# Power_Board_DRV8323.net
KiCad netlist of a schematic drawn in Altium Designer
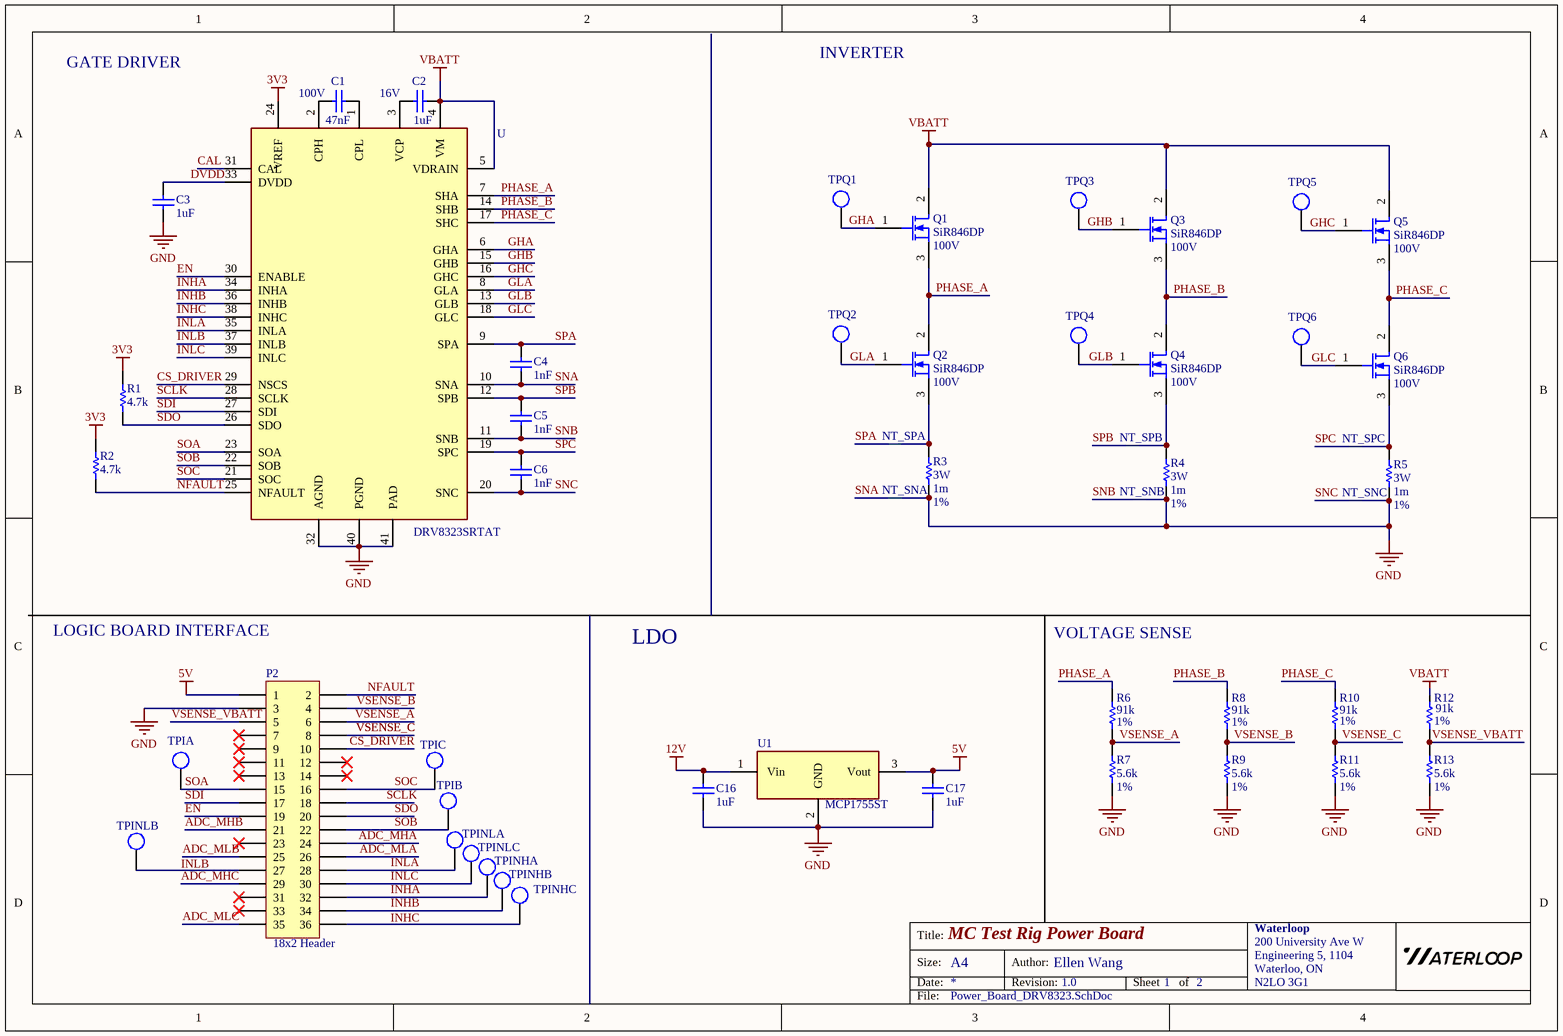
[diagram p0: Power_Board_DRV8323.SchDoc]

(export (version "E")
  (design (tool "Eeschema 10.0.6"))
  (components
    (comp (ref "C1")
      (value "47nF")
      (footprint "0805 - Capacitor")
      (description "Nonpolarized Capacitor")
      (fields
        (field (name "MANUFACTURER") "YAGEO")
        (field (name "RATING") "100V")
        (field (name "MANUFACTURER PART NUMBER") "CC0805KKX7R0BB473")
      )
      (libsource (lib "General") (part "Capacitor - Nonpolarized"))
    )
    (comp (ref "C2")
      (value "1uF")
      (footprint "0805 - Capacitor")
      (description "Nonpolarized Capacitor")
      (fields
        (field (name "MANUFACTURER") "YAGEO")
        (field (name "RATING") "16V")
        (field (name "MANUFACTURER PART NUMBER") "CC0805KKX7R7BB105")
      )
      (libsource (lib "General") (part "Capacitor - Nonpolarized"))
    )
    (comp (ref "C3")
      (value "1uF")
      (footprint "0805 - Capacitor")
      (description "Nonpolarized Capacitor")
      (fields
        (field (name "MANUFACTURER") "YAGEO")
        (field (name "MANUFACTURER PART NUMBER") "CC0805KKX7R7BB105")
      )
      (libsource (lib "General") (part "Capacitor - Nonpolarized"))
    )
    (comp (ref "C4")
      (value "1nF")
      (footprint "0805 - Capacitor")
      (description "Nonpolarized Capacitor")
      (fields
        (field (name "MANUFACTURER") "YAGEO")
        (field (name "MANUFACTURER PART NUMBER") "CC0805KRX7R0BB102")
      )
      (libsource (lib "General") (part "Capacitor - Nonpolarized"))
    )
    (comp (ref "C5")
      (value "1nF")
      (footprint "0805 - Capacitor")
      (description "Nonpolarized Capacitor")
      (fields
        (field (name "MANUFACTURER") "YAGEO")
        (field (name "MANUFACTURER PART NUMBER") "CC0805KRX7R0BB102")
      )
      (libsource (lib "General") (part "Capacitor - Nonpolarized"))
    )
    (comp (ref "C6")
      (value "1nF")
      (footprint "0805 - Capacitor")
      (description "Nonpolarized Capacitor")
      (fields
        (field (name "MANUFACTURER") "YAGEO")
        (field (name "MANUFACTURER PART NUMBER") "CC0805KRX7R0BB102")
      )
      (libsource (lib "General") (part "Capacitor - Nonpolarized"))
    )
    (comp (ref "C16")
      (value "1uF")
      (footprint "0805 - Capacitor")
      (description "Nonpolarized Capacitor")
      (fields (field (name "Comment") "Capacitor - Nonpolarized"))
      (libsource (lib "General") (part "Capacitor - Nonpolarized"))
    )
    (comp (ref "C17")
      (value "1uF")
      (footprint "0805 - Capacitor")
      (description "Nonpolarized Capacitor")
      (fields (field (name "Comment") "Capacitor - Nonpolarized"))
      (libsource (lib "General") (part "Capacitor - Nonpolarized"))
    )
    (comp (ref "NT_SNA") (value "NetTie") (footprint "Net Tie") (libsource (lib "General") (part "Net Tie")))
    (comp (ref "NT_SNB") (value "NetTie") (footprint "Net Tie") (libsource (lib "General") (part "Net Tie")))
    (comp (ref "NT_SNC") (value "NetTie") (footprint "Net Tie") (libsource (lib "General") (part "Net Tie")))
    (comp (ref "NT_SPA") (value "NetTie") (footprint "Net Tie") (libsource (lib "General") (part "Net Tie")))
    (comp (ref "NT_SPB") (value "NetTie") (footprint "Net Tie") (libsource (lib "General") (part "Net Tie")))
    (comp (ref "NT_SPC") (value "NetTie") (footprint "Net Tie") (libsource (lib "General") (part "Net Tie")))
    (comp (ref "P2")
      (value "Header 18X2")
      (footprint "HDR2X18")
      (description "Header, 18-Pin, Dual row")
      (fields (field (name "PUBLISHER") "Altium Limited"))
      (libsource (lib "Miscellaneous Connectors") (part "Header 18X2"))
    )
    (comp (ref "Q1")
      (value "MOSFET-N")
      (footprint "PowerPAK® SO-8")
      (description "N-Channel MOSFET")
      (fields (field (name "SUPPLIER PART NUMBER") "SiR846DP") (field (name "RATING") "100V"))
      (libsource (lib "General") (part "MOSFET-N"))
    )
    (comp (ref "Q2")
      (value "MOSFET-N")
      (footprint "PowerPAK® SO-8")
      (description "N-Channel MOSFET")
      (fields (field (name "SUPPLIER PART NUMBER") "SiR846DP") (field (name "RATING") "100V"))
      (libsource (lib "General") (part "MOSFET-N"))
    )
    (comp (ref "Q3")
      (value "MOSFET-N")
      (footprint "PowerPAK® SO-8")
      (description "N-Channel MOSFET")
      (fields (field (name "SUPPLIER PART NUMBER") "SiR846DP") (field (name "RATING") "100V"))
      (libsource (lib "General") (part "MOSFET-N"))
    )
    (comp (ref "Q4")
      (value "MOSFET-N")
      (footprint "PowerPAK® SO-8")
      (description "N-Channel MOSFET")
      (fields (field (name "SUPPLIER PART NUMBER") "SiR846DP") (field (name "RATING") "100V"))
      (libsource (lib "General") (part "MOSFET-N"))
    )
    (comp (ref "Q5")
      (value "MOSFET-N")
      (footprint "PowerPAK® SO-8")
      (description "N-Channel MOSFET")
      (fields (field (name "SUPPLIER PART NUMBER") "SiR846DP") (field (name "RATING") "100V"))
      (libsource (lib "General") (part "MOSFET-N"))
    )
    (comp (ref "Q6")
      (value "MOSFET-N")
      (footprint "PowerPAK® SO-8")
      (description "N-Channel MOSFET")
      (fields (field (name "SUPPLIER PART NUMBER") "SiR846DP") (field (name "RATING") "100V"))
      (libsource (lib "General") (part "MOSFET-N"))
    )
    (comp (ref "R1")
      (value "4.7k")
      (footprint "0603 - Resistor")
      (description "Resistor")
      (fields
        (field (name "MANUFACTURER PART NUMBER") "RC0603FR-074K7L")
        (field (name "MANUFACTURER") "YAGEO")
      )
      (libsource (lib "General") (part "Resistor"))
    )
    (comp (ref "R2")
      (value "4.7k")
      (footprint "0603 - Resistor")
      (description "Resistor")
      (fields
        (field (name "MANUFACTURER PART NUMBER") "RC0603FR-074K7L")
        (field (name "MANUFACTURER") "YAGEO")
      )
      (libsource (lib "General") (part "Resistor"))
    )
    (comp (ref "R3")
      (value "1m")
      (footprint "2512 - RESISTOR")
      (description "Resistor")
      (fields
        (field (name "RATING") "3W")
        (field (name "MANUFACTURER PART NUMBER") "CSR2512C0R001F")
        (field (name "MANUFACTURER") "Riedon")
        (field (name "TOLERANCE") "1%")
      )
      (libsource (lib "General") (part "Resistor"))
    )
    (comp (ref "R4")
      (value "1m")
      (footprint "2512 - RESISTOR")
      (description "Resistor")
      (fields
        (field (name "RATING") "3W")
        (field (name "MANUFACTURER PART NUMBER") "CSR2512C0R001F")
        (field (name "MANUFACTURER") "Riedon")
        (field (name "TOLERANCE") "1%")
      )
      (libsource (lib "General") (part "Resistor"))
    )
    (comp (ref "R5")
      (value "1m")
      (footprint "2512 - RESISTOR")
      (description "Resistor")
      (fields
        (field (name "RATING") "3W")
        (field (name "MANUFACTURER PART NUMBER") "CSR2512C0R001F")
        (field (name "MANUFACTURER") "Riedon")
        (field (name "TOLERANCE") "1%")
      )
      (libsource (lib "General") (part "Resistor"))
    )
    (comp (ref "R6")
      (value "91k")
      (footprint "0603 - Resistor")
      (description "Resistor")
      (fields
        (field (name "MANUFACTURER PART NUMBER") "RC0603FR-0791KL")
        (field (name "MANUFACTURER") "YAGEO")
        (field (name "TOLERANCE") "1%")
      )
      (libsource (lib "General") (part "Resistor"))
    )
    (comp (ref "R7")
      (value "5.6k")
      (footprint "0603 - Resistor")
      (description "Resistor")
      (fields
        (field (name "MANUFACTURER PART NUMBER") "RC0603FR-075K6L")
        (field (name "MANUFACTURER") "YAGEO")
        (field (name "TOLERANCE") "1%")
      )
      (libsource (lib "General") (part "Resistor"))
    )
    (comp (ref "R8")
      (value "91k")
      (footprint "0603 - Resistor")
      (description "Resistor")
      (fields
        (field (name "MANUFACTURER PART NUMBER") "RC0603FR-0791KL")
        (field (name "MANUFACTURER") "YAGEO")
        (field (name "TOLERANCE") "1%")
      )
      (libsource (lib "General") (part "Resistor"))
    )
    (comp (ref "R9")
      (value "5.6k")
      (footprint "0603 - Resistor")
      (description "Resistor")
      (fields
        (field (name "MANUFACTURER PART NUMBER") "RC0603FR-075K6L")
        (field (name "MANUFACTURER") "YAGEO")
        (field (name "TOLERANCE") "1%")
      )
      (libsource (lib "General") (part "Resistor"))
    )
    (comp (ref "R10")
      (value "91k")
      (footprint "0603 - Resistor")
      (description "Resistor")
      (fields
        (field (name "MANUFACTURER PART NUMBER") "RC0603FR-0791KL")
        (field (name "MANUFACTURER") "YAGEO")
        (field (name "TOLERANCE") "1%")
      )
      (libsource (lib "General") (part "Resistor"))
    )
    (comp (ref "R11")
      (value "5.6k")
      (footprint "0603 - Resistor")
      (description "Resistor")
      (fields
        (field (name "MANUFACTURER PART NUMBER") "RC0603FR-075K6L")
        (field (name "MANUFACTURER") "YAGEO")
        (field (name "TOLERANCE") "1%")
      )
      (libsource (lib "General") (part "Resistor"))
    )
    (comp (ref "R12")
      (value "91k")
      (footprint "0603 - Resistor")
      (description "Resistor")
      (fields
        (field (name "MANUFACTURER PART NUMBER") "RC0603FR-0791KL")
        (field (name "MANUFACTURER") "YAGEO")
        (field (name "TOLERANCE") "1%")
      )
      (libsource (lib "General") (part "Resistor"))
    )
    (comp (ref "R13")
      (value "5.6k")
      (footprint "0603 - Resistor")
      (description "Resistor")
      (fields
        (field (name "MANUFACTURER PART NUMBER") "RC0603FR-075K6L")
        (field (name "MANUFACTURER") "YAGEO")
        (field (name "TOLERANCE") "1%")
      )
      (libsource (lib "General") (part "Resistor"))
    )
    (comp (ref "TPIA")
      (value "Test Point")
      (footprint "Test Point")
      (libsource (lib "General") (part "Test Point"))
    )
    (comp (ref "TPIB")
      (value "Test Point")
      (footprint "Test Point")
      (libsource (lib "General") (part "Test Point"))
    )
    (comp (ref "TPIC")
      (value "Test Point")
      (footprint "Test Point")
      (libsource (lib "General") (part "Test Point"))
    )
    (comp (ref "TPINHA")
      (value "Test Point")
      (footprint "Test Point")
      (libsource (lib "General") (part "Test Point"))
    )
    (comp (ref "TPINHB")
      (value "Test Point")
      (footprint "Test Point")
      (libsource (lib "General") (part "Test Point"))
    )
    (comp (ref "TPINHC")
      (value "Test Point")
      (footprint "Test Point")
      (libsource (lib "General") (part "Test Point"))
    )
    (comp (ref "TPINLA")
      (value "Test Point")
      (footprint "Test Point")
      (libsource (lib "General") (part "Test Point"))
    )
    (comp (ref "TPINLB")
      (value "Test Point")
      (footprint "Test Point")
      (libsource (lib "General") (part "Test Point"))
    )
    (comp (ref "TPINLC")
      (value "Test Point")
      (footprint "Test Point")
      (libsource (lib "General") (part "Test Point"))
    )
    (comp (ref "TPQ1")
      (value "Test Point")
      (footprint "Test Point")
      (libsource (lib "General") (part "Test Point"))
    )
    (comp (ref "TPQ2")
      (value "Test Point")
      (footprint "Test Point")
      (libsource (lib "General") (part "Test Point"))
    )
    (comp (ref "TPQ3")
      (value "Test Point")
      (footprint "Test Point")
      (libsource (lib "General") (part "Test Point"))
    )
    (comp (ref "TPQ4")
      (value "Test Point")
      (footprint "Test Point")
      (libsource (lib "General") (part "Test Point"))
    )
    (comp (ref "TPQ5")
      (value "Test Point")
      (footprint "Test Point")
      (libsource (lib "General") (part "Test Point"))
    )
    (comp (ref "TPQ6")
      (value "Test Point")
      (footprint "Test Point")
      (libsource (lib "General") (part "Test Point"))
    )
    (comp (ref "U")
      (value "DRV8323SRTAT")
      (footprint "DRV8323SRTAT")
      (description "Multiphase Motor Driver Power MOSFET SPI")
      (fields (field (name "MANUFACTURER") "Texas Instruments"))
      (libsource (lib "MC") (part "DRV8323SRTAT"))
    )
    (comp (ref "U1")
      (value "MCP1755ST")
      (footprint "MCP1755ST")
      (libsource (lib "GeneralComponents") (part "MCP1755ST"))
    )
  )
  (nets
    (net (code "1") (name "/ADC_MHA") (class "Default")
      (node (ref "P2") (pin "24") (pinfunction "24_24") (pintype "passive"))
    )
    (net (code "2") (name "/ADC_MHB") (class "Default")
      (node (ref "P2") (pin "21") (pinfunction "21_21") (pintype "passive"))
    )
    (net (code "3") (name "/ADC_MHC") (class "Default")
      (node (ref "P2") (pin "29") (pinfunction "29_29") (pintype "passive"))
    )
    (net (code "4") (name "/ADC_MLA") (class "Default")
      (node (ref "P2") (pin "26") (pinfunction "26_26") (pintype "passive"))
    )
    (net (code "5") (name "/ADC_MLB") (class "Default")
      (node (ref "P2") (pin "25") (pinfunction "25_25") (pintype "passive"))
    )
    (net (code "6") (name "/ADC_MLC") (class "Default")
      (node (ref "P2") (pin "35") (pinfunction "35_35") (pintype "passive"))
    )
    (net (code "7") (name "/CAL") (class "Default")
      (node (ref "U") (pin "31") (pinfunction "CAL_31") (pintype "passive"))
    )
    (net (code "8") (name "/CS_DRIVER") (class "Default")
      (node (ref "P2") (pin "10") (pinfunction "10_10") (pintype "passive"))
      (node (ref "U") (pin "29") (pinfunction "NSCS_29") (pintype "passive"))
    )
    (net (code "9") (name "/DVDD") (class "Default")
      (node (ref "C3") (pin "2") (pinfunction "2_2") (pintype "passive"))
      (node (ref "U") (pin "33") (pinfunction "DVDD_33") (pintype "power_in"))
    )
    (net (code "10") (name "/EN") (class "Default")
      (node (ref "P2") (pin "19") (pinfunction "19_19") (pintype "passive"))
      (node (ref "U") (pin "30") (pinfunction "ENABLE_30") (pintype "passive"))
    )
    (net (code "11") (name "/GHA") (class "Default")
      (node (ref "Q1") (pin "1") (pinfunction "G_1") (pintype "passive"))
      (node (ref "TPQ1") (pin "1") (pinfunction "0_1") (pintype "passive"))
      (node (ref "U") (pin "6") (pinfunction "GHA_6") (pintype "passive"))
    )
    (net (code "12") (name "/GHB") (class "Default")
      (node (ref "Q3") (pin "1") (pinfunction "G_1") (pintype "passive"))
      (node (ref "TPQ3") (pin "1") (pinfunction "0_1") (pintype "passive"))
      (node (ref "U") (pin "15") (pinfunction "GHB_15") (pintype "passive"))
    )
    (net (code "13") (name "/GHC") (class "Default")
      (node (ref "Q5") (pin "1") (pinfunction "G_1") (pintype "passive"))
      (node (ref "TPQ5") (pin "1") (pinfunction "0_1") (pintype "passive"))
      (node (ref "U") (pin "16") (pinfunction "GHC_16") (pintype "passive"))
    )
    (net (code "14") (name "/GLA") (class "Default")
      (node (ref "Q2") (pin "1") (pinfunction "G_1") (pintype "passive"))
      (node (ref "TPQ2") (pin "1") (pinfunction "0_1") (pintype "passive"))
      (node (ref "U") (pin "8") (pinfunction "GLA_8") (pintype "passive"))
    )
    (net (code "15") (name "/GLB") (class "Default")
      (node (ref "Q4") (pin "1") (pinfunction "G_1") (pintype "passive"))
      (node (ref "TPQ4") (pin "1") (pinfunction "0_1") (pintype "passive"))
      (node (ref "U") (pin "13") (pinfunction "GLB_13") (pintype "passive"))
    )
    (net (code "16") (name "/GLC") (class "Default")
      (node (ref "Q6") (pin "1") (pinfunction "G_1") (pintype "passive"))
      (node (ref "TPQ6") (pin "1") (pinfunction "0_1") (pintype "passive"))
      (node (ref "U") (pin "18") (pinfunction "GLC_18") (pintype "passive"))
    )
    (net (code "17") (name "/INHA") (class "Default")
      (node (ref "P2") (pin "32") (pinfunction "32_32") (pintype "passive"))
      (node (ref "TPINHA") (pin "1") (pinfunction "0_1") (pintype "passive"))
      (node (ref "U") (pin "34") (pinfunction "INHA_34") (pintype "passive"))
    )
    (net (code "18") (name "/INHB") (class "Default")
      (node (ref "P2") (pin "34") (pinfunction "34_34") (pintype "passive"))
      (node (ref "TPINHB") (pin "1") (pinfunction "0_1") (pintype "passive"))
      (node (ref "U") (pin "36") (pinfunction "INHB_36") (pintype "passive"))
    )
    (net (code "19") (name "/INHC") (class "Default")
      (node (ref "U") (pin "38") (pinfunction "INHC_38") (pintype "passive"))
    )
    (net (code "20") (name "/INLA") (class "Default")
      (node (ref "P2") (pin "28") (pinfunction "28_28") (pintype "passive"))
      (node (ref "TPINLA") (pin "1") (pinfunction "0_1") (pintype "passive"))
      (node (ref "U") (pin "35") (pinfunction "INLA_35") (pintype "passive"))
    )
    (net (code "21") (name "/INLB") (class "Default")
      (node (ref "U") (pin "37") (pinfunction "INLB_37") (pintype "passive"))
    )
    (net (code "22") (name "/INLC") (class "Default")
      (node (ref "P2") (pin "30") (pinfunction "30_30") (pintype "passive"))
      (node (ref "TPINLC") (pin "1") (pinfunction "0_1") (pintype "passive"))
      (node (ref "U") (pin "39") (pinfunction "INLC_39") (pintype "passive"))
    )
    (net (code "23") (name "/NFAULT") (class "Default")
      (node (ref "P2") (pin "2") (pinfunction "2_2") (pintype "passive"))
      (node (ref "R2") (pin "1") (pinfunction "1_1") (pintype "passive"))
      (node (ref "U") (pin "25") (pinfunction "NFAULT_25") (pintype "passive"))
    )
    (net (code "24") (name "/PHASE_A") (class "Default")
      (node (ref "Q1") (pin "3") (pinfunction "S_3") (pintype "passive"))
      (node (ref "Q2") (pin "2") (pinfunction "D_2") (pintype "passive"))
      (node (ref "R6") (pin "1") (pinfunction "1_1") (pintype "passive"))
      (node (ref "U") (pin "7") (pinfunction "SHA_7") (pintype "passive"))
    )
    (net (code "25") (name "/PHASE_B") (class "Default")
      (node (ref "Q3") (pin "3") (pinfunction "S_3") (pintype "passive"))
      (node (ref "Q4") (pin "2") (pinfunction "D_2") (pintype "passive"))
      (node (ref "R8") (pin "1") (pinfunction "1_1") (pintype "passive"))
      (node (ref "U") (pin "14") (pinfunction "SHB_14") (pintype "passive"))
    )
    (net (code "26") (name "/PHASE_C") (class "Default")
      (node (ref "Q5") (pin "3") (pinfunction "S_3") (pintype "passive"))
      (node (ref "Q6") (pin "2") (pinfunction "D_2") (pintype "passive"))
      (node (ref "R10") (pin "1") (pinfunction "1_1") (pintype "passive"))
      (node (ref "U") (pin "17") (pinfunction "SHC_17") (pintype "passive"))
    )
    (net (code "27") (name "/SCLK") (class "Default")
      (node (ref "P2") (pin "18") (pinfunction "18_18") (pintype "passive"))
      (node (ref "U") (pin "28") (pinfunction "SCLK_28") (pintype "passive"))
    )
    (net (code "28") (name "/SDI") (class "Default")
      (node (ref "P2") (pin "17") (pinfunction "17_17") (pintype "passive"))
      (node (ref "U") (pin "27") (pinfunction "SDI_27") (pintype "passive"))
    )
    (net (code "29") (name "/SDO") (class "Default")
      (node (ref "P2") (pin "20") (pinfunction "20_20") (pintype "passive"))
      (node (ref "R1") (pin "1") (pinfunction "1_1") (pintype "passive"))
      (node (ref "U") (pin "26") (pinfunction "SDO_26") (pintype "passive"))
    )
    (net (code "30") (name "/SNA") (class "Default")
      (node (ref "C4") (pin "1") (pinfunction "1_1") (pintype "passive"))
      (node (ref "NT_SNA") (pin "1") (pinfunction "1_1") (pintype "passive"))
      (node (ref "U") (pin "10") (pinfunction "SNA_10") (pintype "passive"))
    )
    (net (code "31") (name "/SNB") (class "Default")
      (node (ref "C5") (pin "1") (pinfunction "1_1") (pintype "passive"))
      (node (ref "NT_SNB") (pin "1") (pinfunction "1_1") (pintype "passive"))
      (node (ref "U") (pin "11") (pinfunction "SNB_11") (pintype "passive"))
    )
    (net (code "32") (name "/SNC") (class "Default")
      (node (ref "C6") (pin "1") (pinfunction "1_1") (pintype "passive"))
      (node (ref "NT_SNC") (pin "1") (pinfunction "1_1") (pintype "passive"))
      (node (ref "U") (pin "20") (pinfunction "SNC_20") (pintype "passive"))
    )
    (net (code "33") (name "/SOA") (class "Default")
      (node (ref "P2") (pin "15") (pinfunction "15_15") (pintype "passive"))
      (node (ref "TPIA") (pin "1") (pinfunction "0_1") (pintype "passive"))
      (node (ref "U") (pin "23") (pinfunction "SOA_23") (pintype "passive"))
    )
    (net (code "34") (name "/SOB") (class "Default")
      (node (ref "P2") (pin "22") (pinfunction "22_22") (pintype "passive"))
      (node (ref "TPIB") (pin "1") (pinfunction "0_1") (pintype "passive"))
      (node (ref "U") (pin "22") (pinfunction "SOB_22") (pintype "passive"))
    )
    (net (code "35") (name "/SOC") (class "Default")
      (node (ref "P2") (pin "16") (pinfunction "16_16") (pintype "passive"))
      (node (ref "TPIC") (pin "1") (pinfunction "0_1") (pintype "passive"))
      (node (ref "U") (pin "21") (pinfunction "SOC_21") (pintype "passive"))
    )
    (net (code "36") (name "/SPA") (class "Default")
      (node (ref "C4") (pin "2") (pinfunction "2_2") (pintype "passive"))
      (node (ref "NT_SPA") (pin "1") (pinfunction "1_1") (pintype "passive"))
      (node (ref "U") (pin "9") (pinfunction "SPA_9") (pintype "passive"))
    )
    (net (code "37") (name "/SPB") (class "Default")
      (node (ref "C5") (pin "2") (pinfunction "2_2") (pintype "passive"))
      (node (ref "NT_SPB") (pin "1") (pinfunction "1_1") (pintype "passive"))
      (node (ref "U") (pin "12") (pinfunction "SPB_12") (pintype "passive"))
    )
    (net (code "38") (name "/SPC") (class "Default")
      (node (ref "C6") (pin "2") (pinfunction "2_2") (pintype "passive"))
      (node (ref "NT_SPC") (pin "1") (pinfunction "1_1") (pintype "passive"))
      (node (ref "U") (pin "19") (pinfunction "SPC_19") (pintype "passive"))
    )
    (net (code "39") (name "/VSENSE_A") (class "Default")
      (node (ref "P2") (pin "6") (pinfunction "6_6") (pintype "passive"))
      (node (ref "R6") (pin "2") (pinfunction "2_2") (pintype "passive"))
      (node (ref "R7") (pin "1") (pinfunction "1_1") (pintype "passive"))
    )
    (net (code "40") (name "/VSENSE_B") (class "Default")
      (node (ref "P2") (pin "4") (pinfunction "4_4") (pintype "passive"))
      (node (ref "R8") (pin "2") (pinfunction "2_2") (pintype "passive"))
      (node (ref "R9") (pin "1") (pinfunction "1_1") (pintype "passive"))
    )
    (net (code "41") (name "/VSENSE_C") (class "Default")
      (node (ref "P2") (pin "8") (pinfunction "8_8") (pintype "passive"))
      (node (ref "R10") (pin "2") (pinfunction "2_2") (pintype "passive"))
      (node (ref "R11") (pin "1") (pinfunction "1_1") (pintype "passive"))
    )
    (net (code "42") (name "/VSENSE_VBATT") (class "Default")
      (node (ref "P2") (pin "5") (pinfunction "5_5") (pintype "passive"))
      (node (ref "R12") (pin "2") (pinfunction "2_2") (pintype "passive"))
      (node (ref "R13") (pin "1") (pinfunction "1_1") (pintype "passive"))
    )
    (net (code "43") (name "3V3") (class "Default")
      (node (ref "R1") (pin "2") (pinfunction "2_2") (pintype "passive"))
      (node (ref "R2") (pin "2") (pinfunction "2_2") (pintype "passive"))
      (node (ref "U") (pin "24") (pinfunction "VREF_24") (pintype "power_in"))
    )
    (net (code "44") (name "5V") (class "Default")
      (node (ref "C17") (pin "2") (pinfunction "2_2") (pintype "passive"))
      (node (ref "P2") (pin "1") (pinfunction "1_1") (pintype "passive"))
      (node (ref "U1") (pin "3") (pinfunction "Vout_3") (pintype "passive"))
    )
    (net (code "45") (name "12V") (class "Default")
      (node (ref "C16") (pin "2") (pinfunction "2_2") (pintype "passive"))
      (node (ref "U1") (pin "1") (pinfunction "Vin_1") (pintype "passive"))
    )
    (net (code "46") (name "GND") (class "Default")
      (node (ref "C16") (pin "1") (pinfunction "1_1") (pintype "passive"))
      (node (ref "C17") (pin "1") (pinfunction "1_1") (pintype "passive"))
      (node (ref "C3") (pin "1") (pinfunction "1_1") (pintype "passive"))
      (node (ref "NT_SNA") (pin "2") (pinfunction "2_2") (pintype "passive"))
      (node (ref "NT_SNB") (pin "2") (pinfunction "2_2") (pintype "passive"))
      (node (ref "NT_SNC") (pin "2") (pinfunction "2_2") (pintype "passive"))
      (node (ref "P2") (pin "3") (pinfunction "3_3") (pintype "passive"))
      (node (ref "R11") (pin "2") (pinfunction "2_2") (pintype "passive"))
      (node (ref "R13") (pin "2") (pinfunction "2_2") (pintype "passive"))
      (node (ref "R3") (pin "1") (pinfunction "1_1") (pintype "passive"))
      (node (ref "R4") (pin "1") (pinfunction "1_1") (pintype "passive"))
      (node (ref "R5") (pin "1") (pinfunction "1_1") (pintype "passive"))
      (node (ref "R7") (pin "2") (pinfunction "2_2") (pintype "passive"))
      (node (ref "R9") (pin "2") (pinfunction "2_2") (pintype "passive"))
      (node (ref "U1") (pin "2") (pinfunction "GND_2") (pintype "passive"))
    )
    (net (code "47") (name "Net-(Q2-S)") (class "Default")
      (node (ref "NT_SPA") (pin "2") (pinfunction "2_2") (pintype "passive"))
      (node (ref "Q2") (pin "3") (pinfunction "S_3") (pintype "passive"))
      (node (ref "R3") (pin "2") (pinfunction "2_2") (pintype "passive"))
    )
    (net (code "48") (name "Net-(Q4-S)") (class "Default")
      (node (ref "NT_SPB") (pin "2") (pinfunction "2_2") (pintype "passive"))
      (node (ref "Q4") (pin "3") (pinfunction "S_3") (pintype "passive"))
      (node (ref "R4") (pin "2") (pinfunction "2_2") (pintype "passive"))
    )
    (net (code "49") (name "Net-(Q6-S)") (class "Default")
      (node (ref "NT_SPC") (pin "2") (pinfunction "2_2") (pintype "passive"))
      (node (ref "Q6") (pin "3") (pinfunction "S_3") (pintype "passive"))
      (node (ref "R5") (pin "2") (pinfunction "2_2") (pintype "passive"))
    )
    (net (code "50") (name "Net-(TPINHC-0)") (class "Default")
      (node (ref "P2") (pin "36") (pinfunction "36_36") (pintype "passive"))
      (node (ref "TPINHC") (pin "1") (pinfunction "0_1") (pintype "passive"))
    )
    (net (code "51") (name "Net-(TPINLB-0)") (class "Default")
      (node (ref "P2") (pin "27") (pinfunction "27_27") (pintype "passive"))
      (node (ref "TPINLB") (pin "1") (pinfunction "0_1") (pintype "passive"))
    )
    (net (code "52") (name "Net-(U-AGND)") (class "Default")
      (node (ref "U") (pin "32") (pinfunction "AGND_32") (pintype "power_in"))
      (node (ref "U") (pin "40") (pinfunction "PGND_40") (pintype "power_in"))
      (node (ref "U") (pin "41") (pinfunction "PAD_41") (pintype "power_in"))
    )
    (net (code "53") (name "Net-(U-CPH)") (class "Default")
      (node (ref "C1") (pin "1") (pinfunction "1_1") (pintype "passive"))
      (node (ref "U") (pin "2") (pinfunction "CPH_2") (pintype "power_in"))
    )
    (net (code "54") (name "Net-(U-CPL)") (class "Default")
      (node (ref "C1") (pin "2") (pinfunction "2_2") (pintype "passive"))
      (node (ref "U") (pin "1") (pinfunction "CPL_1") (pintype "power_in"))
    )
    (net (code "55") (name "Net-(U-VCP)") (class "Default")
      (node (ref "C2") (pin "1") (pinfunction "1_1") (pintype "passive"))
      (node (ref "U") (pin "3") (pinfunction "VCP_3") (pintype "power_in"))
    )
    (net (code "56") (name "VBATT") (class "Default")
      (node (ref "C2") (pin "2") (pinfunction "2_2") (pintype "passive"))
      (node (ref "Q1") (pin "2") (pinfunction "D_2") (pintype "passive"))
      (node (ref "Q3") (pin "2") (pinfunction "D_2") (pintype "passive"))
      (node (ref "Q5") (pin "2") (pinfunction "D_2") (pintype "passive"))
      (node (ref "R12") (pin "1") (pinfunction "1_1") (pintype "passive"))
      (node (ref "U") (pin "4") (pinfunction "VM_4") (pintype "power_in"))
      (node (ref "U") (pin "5") (pinfunction "VDRAIN_5") (pintype "passive"))
    )
    (net (code "57") (name "unconnected-(P2-Pad7)") (class "Default")
      (node (ref "P2") (pin "7") (pinfunction "7_7") (pintype "passive+no_connect"))
    )
    (net (code "58") (name "unconnected-(P2-Pad9)") (class "Default")
      (node (ref "P2") (pin "9") (pinfunction "9_9") (pintype "passive+no_connect"))
    )
    (net (code "59") (name "unconnected-(P2-Pad11)") (class "Default")
      (node (ref "P2") (pin "11") (pinfunction "11_11") (pintype "passive+no_connect"))
    )
    (net (code "60") (name "unconnected-(P2-Pad12)") (class "Default")
      (node (ref "P2") (pin "12") (pinfunction "12_12") (pintype "passive+no_connect"))
    )
    (net (code "61") (name "unconnected-(P2-Pad13)") (class "Default")
      (node (ref "P2") (pin "13") (pinfunction "13_13") (pintype "passive+no_connect"))
    )
    (net (code "62") (name "unconnected-(P2-Pad14)") (class "Default")
      (node (ref "P2") (pin "14") (pinfunction "14_14") (pintype "passive+no_connect"))
    )
    (net (code "63") (name "unconnected-(P2-Pad23)") (class "Default")
      (node (ref "P2") (pin "23") (pinfunction "23_23") (pintype "passive+no_connect"))
    )
    (net (code "64") (name "unconnected-(P2-Pad31)") (class "Default")
      (node (ref "P2") (pin "31") (pinfunction "31_31") (pintype "passive+no_connect"))
    )
    (net (code "65") (name "unconnected-(P2-Pad33)") (class "Default")
      (node (ref "P2") (pin "33") (pinfunction "33_33") (pintype "passive+no_connect"))
    )
  )
)
